# Cont_Brain.net
KiCad netlist of a schematic drawn in Altium Designer
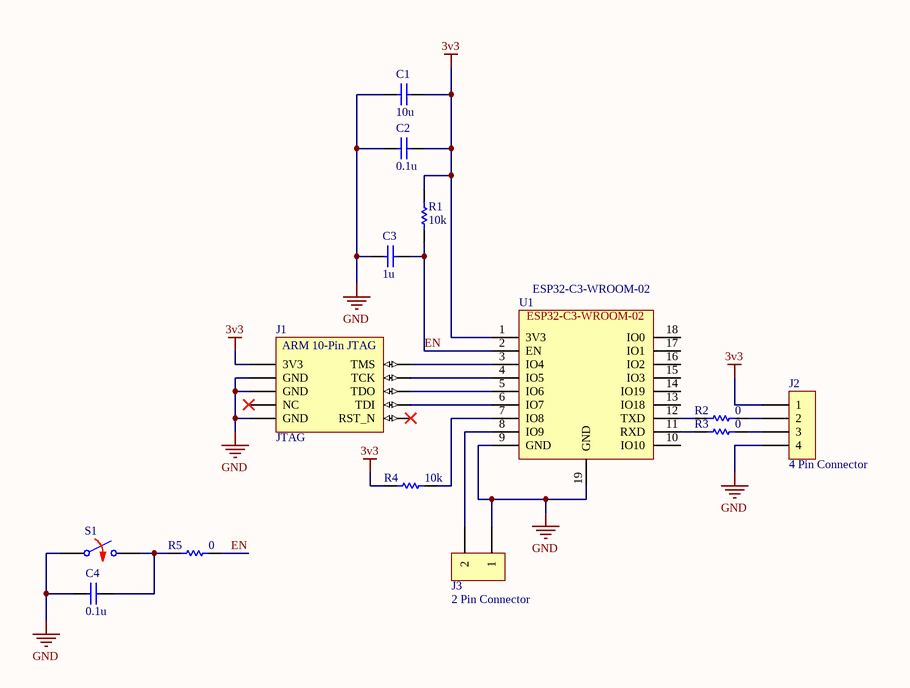
[diagram p0: Cont_Brain.SchDoc]

(export (version "E")
  (design (tool "Eeschema 10.0.6"))
  (components
    (comp (ref "C1")
      (value "10u")
      (description "Capacitor")
      (libsource (lib "Simulation Generic Components") (part "Capacitor"))
    )
    (comp (ref "C2")
      (value "0.1u")
      (description "Capacitor")
      (libsource (lib "Simulation Generic Components") (part "Capacitor"))
    )
    (comp (ref "C3")
      (value "1u")
      (description "Capacitor")
      (libsource (lib "Simulation Generic Components") (part "Capacitor"))
    )
    (comp (ref "C4")
      (value "0.1u")
      (description "Capacitor")
      (libsource (lib "Simulation Generic Components") (part "Capacitor"))
    )
    (comp (ref "J1")
      (value "JTAG")
      (description "Genaric JTAG Arm 10-Pin (Cortex Debug) Header")
      (libsource (lib "UVSD_Symbols") (part "JTAG"))
    )
    (comp (ref "J2")
      (value "4 Pin Connector")
      (footprint "HW_M20_99904XX")
      (libsource (lib "UVSD_Symbols") (part "4 Pin Connector"))
    )
    (comp (ref "J3") (value "2 Pin Connector") (libsource (lib "UVSD_Symbols") (part "2 Pin Connector")))
    (comp (ref "R1")
      (value "10k")
      (description "Resistor")
      (libsource (lib "Simulation Generic Components") (part "Resistor"))
    )
    (comp (ref "R2")
      (value "0")
      (description "Resistor")
      (libsource (lib "Simulation Generic Components") (part "Resistor"))
    )
    (comp (ref "R3")
      (value "0")
      (description "Resistor")
      (libsource (lib "Simulation Generic Components") (part "Resistor"))
    )
    (comp (ref "R4")
      (value "10k")
      (description "Resistor")
      (libsource (lib "Simulation Generic Components") (part "Resistor"))
    )
    (comp (ref "R5")
      (value "0")
      (description "Resistor")
      (libsource (lib "Simulation Generic Components") (part "Resistor"))
    )
    (comp (ref "S1")
      (value "Switch Normally Opened")
      (footprint "SW_SWT0310-043016GSA_REVA")
      (libsource (lib "Simulation Generic Components") (part "SW NO"))
    )
    (comp (ref "U1") (value "ESP32-C3-WROOM-02") (libsource (lib "BW_Library") (part "ESP32-C3-WROOM-02")))
  )
  (nets
    (net (code "1") (name "/EN") (class "Default")
      (node (ref "C3") (pin "2") (pinfunction "2_2") (pintype "passive"))
      (node (ref "R1") (pin "2") (pinfunction "2_2") (pintype "passive"))
      (node (ref "R5") (pin "1") (pinfunction "1_1") (pintype "passive"))
      (node (ref "U1") (pin "2") (pinfunction "EN_2") (pintype "passive"))
    )
    (net (code "2") (name "3v3") (class "Default")
      (node (ref "C1") (pin "2") (pinfunction "2_2") (pintype "passive"))
      (node (ref "C2") (pin "2") (pinfunction "2_2") (pintype "passive"))
      (node (ref "J1") (pin "1") (pinfunction "3V3_1") (pintype "power_in"))
      (node (ref "J2") (pin "1") (pinfunction "1_1") (pintype "passive"))
      (node (ref "R1") (pin "1") (pinfunction "1_1") (pintype "passive"))
      (node (ref "R4") (pin "2") (pinfunction "2_2") (pintype "passive"))
      (node (ref "U1") (pin "1") (pinfunction "3V3_1") (pintype "passive"))
    )
    (net (code "3") (name "GND") (class "Default")
      (node (ref "C1") (pin "1") (pinfunction "1_1") (pintype "passive"))
      (node (ref "C2") (pin "1") (pinfunction "1_1") (pintype "passive"))
      (node (ref "C3") (pin "1") (pinfunction "1_1") (pintype "passive"))
      (node (ref "C4") (pin "1") (pinfunction "1_1") (pintype "passive"))
      (node (ref "J1") (pin "3") (pinfunction "GND_3") (pintype "power_in"))
      (node (ref "J1") (pin "5") (pinfunction "GND_5") (pintype "power_in"))
      (node (ref "J1") (pin "9") (pinfunction "GND_9") (pintype "power_in"))
      (node (ref "J2") (pin "4") (pinfunction "4_4") (pintype "passive"))
      (node (ref "J3") (pin "1") (pinfunction "1_1") (pintype "passive"))
      (node (ref "S1") (pin "1") (pinfunction "1_1") (pintype "passive"))
      (node (ref "U1") (pin "19") (pinfunction "GND_19") (pintype "passive"))
      (node (ref "U1") (pin "9") (pinfunction "GND_9") (pintype "passive"))
    )
    (net (code "4") (name "Net-(C4-Pad2)") (class "Default")
      (node (ref "C4") (pin "2") (pinfunction "2_2") (pintype "passive"))
      (node (ref "R5") (pin "2") (pinfunction "2_2") (pintype "passive"))
      (node (ref "S1") (pin "2") (pinfunction "2_2") (pintype "passive"))
    )
    (net (code "5") (name "Net-(J1-TCK)") (class "Default")
      (node (ref "J1") (pin "4") (pinfunction "TCK_4") (pintype "bidirectional"))
      (node (ref "U1") (pin "4") (pinfunction "IO5_4") (pintype "passive"))
    )
    (net (code "6") (name "Net-(J1-TDI)") (class "Default")
      (node (ref "J1") (pin "8") (pinfunction "TDI_8") (pintype "bidirectional"))
      (node (ref "U1") (pin "6") (pinfunction "IO7_6") (pintype "passive"))
    )
    (net (code "7") (name "Net-(J1-TDO)") (class "Default")
      (node (ref "J1") (pin "6") (pinfunction "TDO_6") (pintype "bidirectional"))
      (node (ref "U1") (pin "5") (pinfunction "IO6_5") (pintype "passive"))
    )
    (net (code "8") (name "Net-(J1-TMS)") (class "Default")
      (node (ref "J1") (pin "2") (pinfunction "TMS_2") (pintype "bidirectional"))
      (node (ref "U1") (pin "3") (pinfunction "IO4_3") (pintype "passive"))
    )
    (net (code "9") (name "Net-(J2-Pad2)") (class "Default")
      (node (ref "J2") (pin "2") (pinfunction "2_2") (pintype "passive"))
      (node (ref "R2") (pin "1") (pinfunction "1_1") (pintype "passive"))
    )
    (net (code "10") (name "Net-(J2-Pad3)") (class "Default")
      (node (ref "J2") (pin "3") (pinfunction "3_3") (pintype "passive"))
      (node (ref "R3") (pin "1") (pinfunction "1_1") (pintype "passive"))
    )
    (net (code "11") (name "Net-(U1-IO8)") (class "Default")
      (node (ref "R4") (pin "1") (pinfunction "1_1") (pintype "passive"))
      (node (ref "U1") (pin "7") (pinfunction "IO8_7") (pintype "passive"))
    )
    (net (code "12") (name "Net-(U1-IO9)") (class "Default")
      (node (ref "J3") (pin "2") (pinfunction "2_2") (pintype "passive"))
      (node (ref "U1") (pin "8") (pinfunction "IO9_8") (pintype "passive"))
    )
    (net (code "13") (name "Net-(U1-RXD)") (class "Default")
      (node (ref "R3") (pin "2") (pinfunction "2_2") (pintype "passive"))
      (node (ref "U1") (pin "11") (pinfunction "RXD_11") (pintype "passive"))
    )
    (net (code "14") (name "Net-(U1-TXD)") (class "Default")
      (node (ref "R2") (pin "2") (pinfunction "2_2") (pintype "passive"))
      (node (ref "U1") (pin "12") (pinfunction "TXD_12") (pintype "passive"))
    )
    (net (code "15") (name "unconnected-(J1-NC-Pad7)") (class "Default")
      (node (ref "J1") (pin "7") (pinfunction "NC_7") (pintype "power_in+no_connect"))
    )
    (net (code "16") (name "unconnected-(J1-RST_N-Pad10)") (class "Default")
      (node (ref "J1") (pin "10") (pinfunction "RST_N_10") (pintype "bidirectional+no_connect"))
    )
    (net (code "17") (name "unconnected-(U1-IO0-Pad18)") (class "Default")
      (node (ref "U1") (pin "18") (pinfunction "IO0_18") (pintype "passive"))
    )
    (net (code "18") (name "unconnected-(U1-IO1-Pad17)") (class "Default")
      (node (ref "U1") (pin "17") (pinfunction "IO1_17") (pintype "passive"))
    )
    (net (code "19") (name "unconnected-(U1-IO2-Pad16)") (class "Default")
      (node (ref "U1") (pin "16") (pinfunction "IO2_16") (pintype "passive"))
    )
    (net (code "20") (name "unconnected-(U1-IO3-Pad15)") (class "Default")
      (node (ref "U1") (pin "15") (pinfunction "IO3_15") (pintype "passive"))
    )
    (net (code "21") (name "unconnected-(U1-IO10-Pad10)") (class "Default")
      (node (ref "U1") (pin "10") (pinfunction "IO10_10") (pintype "passive"))
    )
    (net (code "22") (name "unconnected-(U1-IO18-Pad13)") (class "Default")
      (node (ref "U1") (pin "13") (pinfunction "IO18_13") (pintype "passive"))
    )
    (net (code "23") (name "unconnected-(U1-IO19-Pad14)") (class "Default")
      (node (ref "U1") (pin "14") (pinfunction "IO19_14") (pintype "passive"))
    )
  )
)
